# 12V-input-filter.net
KiCad netlist of a schematic drawn in EAGLE
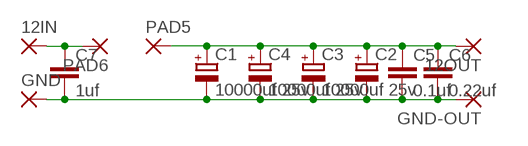
[diagram p0: schematic, sheet 1]

(export (version "E")
  (design (tool "Eeschema 10.0.6"))
  (components
    (comp (ref "12IN")
      (value "3,81/1,4")
      (footprint "eagle-import:3,81_1,4")
      (libsource (lib "eagle-import") (part "3,81/1,4"))
    )
    (comp (ref "12OUT")
      (value "3,81/1,4")
      (footprint "eagle-import:3,81_1,4")
      (libsource (lib "eagle-import") (part "3,81/1,4"))
    )
    (comp (ref "C1")
      (value "10000uf 25v")
      (footprint "eagle-import:EB22,5D")
      (libsource (lib "eagle-import") (part "CPOL-EUE10-22.5"))
    )
    (comp (ref "C2")
      (value "CPOL-EUE10-22.5")
      (footprint "eagle-import:EB22,5D")
      (libsource (lib "eagle-import") (part "CPOL-EUE10-22.5"))
    )
    (comp (ref "C3")
      (value "10000uf 25v")
      (footprint "eagle-import:EB22,5D")
      (libsource (lib "eagle-import") (part "CPOL-EUE10-22.5"))
    )
    (comp (ref "C4")
      (value "10000uf 25v")
      (footprint "eagle-import:EB22,5D")
      (libsource (lib "eagle-import") (part "CPOL-EUE10-22.5"))
    )
    (comp (ref "C5")
      (value "0.1uf")
      (footprint "eagle-import:C150-064X183")
      (libsource (lib "eagle-import") (part "C-EU150-064X183"))
    )
    (comp (ref "C6")
      (value "0.22uf")
      (footprint "eagle-import:C150-064X183")
      (libsource (lib "eagle-import") (part "C-EU150-064X183"))
    )
    (comp (ref "C7")
      (value "1uf")
      (footprint "eagle-import:C150-064X183")
      (libsource (lib "eagle-import") (part "C-EU150-064X183"))
    )
    (comp (ref "GND")
      (value "3,81/1,4")
      (footprint "eagle-import:3,81_1,4")
      (libsource (lib "eagle-import") (part "3,81/1,4"))
    )
    (comp (ref "GND-OUT")
      (value "3,81/1,4")
      (footprint "eagle-import:3,81_1,4")
      (libsource (lib "eagle-import") (part "3,81/1,4"))
    )
    (comp (ref "PAD5")
      (value "3,81/1,4")
      (footprint "eagle-import:3,81_1,4")
      (libsource (lib "eagle-import") (part "3,81/1,4"))
    )
    (comp (ref "PAD6")
      (value "3,81/1,4")
      (footprint "eagle-import:3,81_1,4")
      (libsource (lib "eagle-import") (part "3,81/1,4"))
    )
  )
  (nets
    (net (code "1") (name "Net-(12IN-P)") (class "Default")
      (node (ref "12IN") (pin "1") (pinfunction "P_1") (pintype "passive"))
      (node (ref "C7") (pin "1") (pinfunction "1_1") (pintype "passive"))
      (node (ref "PAD6") (pin "1") (pinfunction "P_1") (pintype "passive"))
    )
    (net (code "2") (name "Net-(12OUT-P)") (class "Default")
      (node (ref "12OUT") (pin "1") (pinfunction "P_1") (pintype "passive"))
      (node (ref "C1") (pin "+") (pinfunction "+_+") (pintype "passive"))
      (node (ref "C2") (pin "+") (pinfunction "+_+") (pintype "passive"))
      (node (ref "C3") (pin "+") (pinfunction "+_+") (pintype "passive"))
      (node (ref "C4") (pin "+") (pinfunction "+_+") (pintype "passive"))
      (node (ref "C5") (pin "1") (pinfunction "1_1") (pintype "passive"))
      (node (ref "C6") (pin "1") (pinfunction "1_1") (pintype "passive"))
      (node (ref "PAD5") (pin "1") (pinfunction "P_1") (pintype "passive"))
    )
    (net (code "3") (name "Net-(GND-OUT-P)") (class "Default")
      (node (ref "C1") (pin "-") (pinfunction "-_-") (pintype "passive"))
      (node (ref "C2") (pin "-") (pinfunction "-_-") (pintype "passive"))
      (node (ref "C3") (pin "-") (pinfunction "-_-") (pintype "passive"))
      (node (ref "C4") (pin "-") (pinfunction "-_-") (pintype "passive"))
      (node (ref "C5") (pin "2") (pinfunction "2_2") (pintype "passive"))
      (node (ref "C6") (pin "2") (pinfunction "2_2") (pintype "passive"))
      (node (ref "C7") (pin "2") (pinfunction "2_2") (pintype "passive"))
      (node (ref "GND") (pin "1") (pinfunction "P_1") (pintype "passive"))
      (node (ref "GND-OUT") (pin "1") (pinfunction "P_1") (pintype "passive"))
    )
  )
)
